# -404-19.net
KiCad netlist of a schematic drawn in Altium Designer
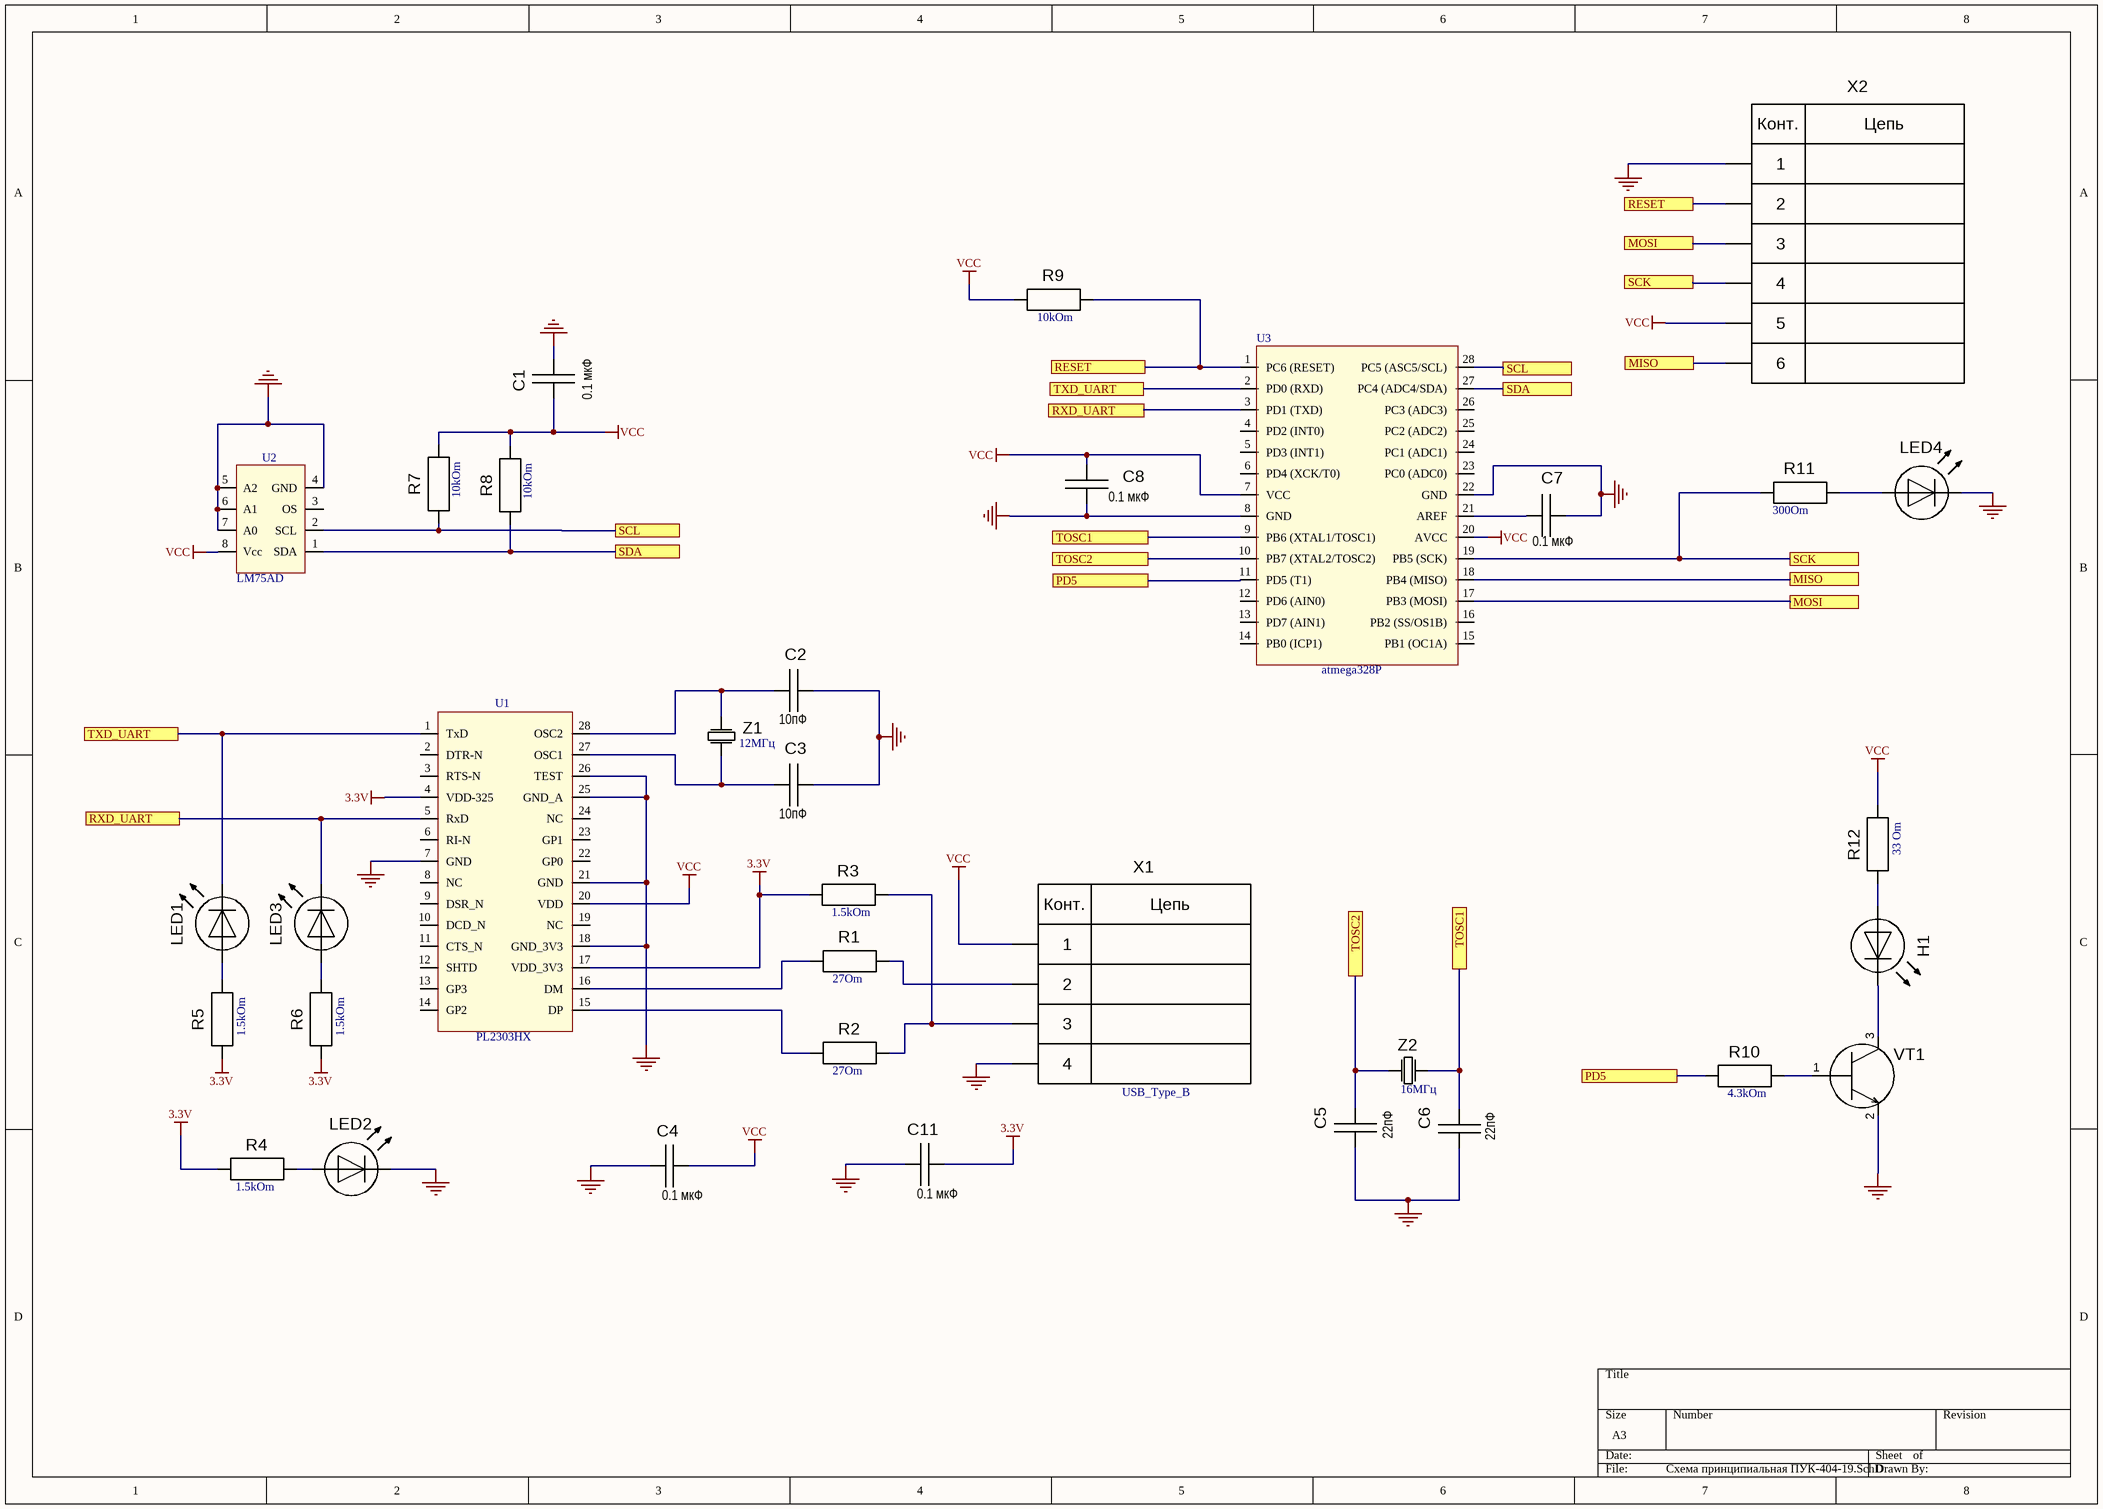
[diagram p0: Схема принципиальная ПУК-404-19.SchDoc]

(export (version "E")
  (design (tool "Eeschema 10.0.6"))
  (components
    (comp (ref "C1") (value "0.1 мкФ") (footprint "C_1206") (libsource (lib "") (part "C_1")))
    (comp (ref "C2") (value "10пФ") (footprint "C_0805") (libsource (lib "Passive") (part "C")))
    (comp (ref "C3") (value "10пФ") (footprint "C_0805") (libsource (lib "Passive") (part "C")))
    (comp (ref "C4") (value "0.1 мкФ") (footprint "C_1206") (libsource (lib "Passive") (part "C")))
    (comp (ref "C5") (value "22пФ") (footprint "C_1206") (libsource (lib "Passive") (part "C")))
    (comp (ref "C6") (value "22пФ") (footprint "C_1206") (libsource (lib "Passive") (part "C")))
    (comp (ref "C7") (value "0.1 мкФ") (footprint "C_1206") (libsource (lib "Passive") (part "C")))
    (comp (ref "C8") (value "0.1 мкФ") (footprint "C_1206") (libsource (lib "Passive") (part "C")))
    (comp (ref "C11") (value "0.1 мкФ") (footprint "C_1206") (libsource (lib "Passive") (part "C")))
    (comp (ref "H1") (value "TSAL6200") (footprint "ledrad3mm") (libsource (lib "VD") (part "LED")))
    (comp (ref "LED1") (value "LED") (footprint "ledrad3mm") (libsource (lib "VD") (part "LED")))
    (comp (ref "LED2") (value "LED") (footprint "ledrad3mm") (libsource (lib "VD") (part "LED")))
    (comp (ref "LED3") (value "LED") (footprint "ledrad3mm") (libsource (lib "VD") (part "LED")))
    (comp (ref "LED4") (value "LED") (footprint "ledrad3mm") (libsource (lib "VD") (part "LED")))
    (comp (ref "R1") (value "27Om") (footprint "R_1206") (libsource (lib "Passive") (part "Resistor")))
    (comp (ref "R2") (value "27Om") (footprint "R_1206") (libsource (lib "Passive") (part "Resistor")))
    (comp (ref "R3") (value "1.5kOm") (footprint "R_1206") (libsource (lib "Passive") (part "Resistor")))
    (comp (ref "R4") (value "1.5kOm") (footprint "R_1206") (libsource (lib "Passive") (part "Resistor")))
    (comp (ref "R5") (value "1.5kOm") (footprint "R_1206") (libsource (lib "Passive") (part "Resistor")))
    (comp (ref "R6") (value "1.5kOm") (footprint "R_1206") (libsource (lib "Passive") (part "Resistor")))
    (comp (ref "R7") (value "10kOm") (footprint "R_1206") (libsource (lib "Passive") (part "Resistor")))
    (comp (ref "R8") (value "10kOm") (footprint "R_1206") (libsource (lib "Passive") (part "Resistor")))
    (comp (ref "R9") (value "10kOm") (footprint "R_1206") (libsource (lib "Passive") (part "Resistor")))
    (comp (ref "R10") (value "4.3kOm") (footprint "R_1206") (libsource (lib "Passive") (part "Resistor")))
    (comp (ref "R11") (value "300Om") (footprint "R_1206") (libsource (lib "Passive") (part "Resistor")))
    (comp (ref "R12") (value "33 Om") (footprint "R_1206") (libsource (lib "Passive") (part "Resistor")))
    (comp (ref "U1") (value "PL2303HX") (footprint "SO-28W") (libsource (lib "PL2303HX") (part "PL2303HX")))
    (comp (ref "U2") (value "LM75AD") (footprint "TSSOP8") (libsource (lib "A75AD") (part "LM75AD")))
    (comp (ref "U3")
      (value "atmega328P")
      (footprint "27_DIP_7.62mm")
      (libsource (lib "ATMEGA328P") (part "Atmega328P"))
    )
    (comp (ref "VT1") (value "BC547") (footprint "TO-92-CBE") (libsource (lib "VT") (part "NPN_BEC")))
    (comp (ref "X1")
      (value "USB_Type_B")
      (footprint "USB_TypeB_Tyco")
      (libsource (lib "Connectors") (part "X_4"))
    )
    (comp (ref "X2") (value "X_6") (footprint "PLD-6") (libsource (lib "Connectors") (part "X_6")))
    (comp (ref "Z1") (value "12МГц") (footprint "HC-49H") (libsource (lib "") (part "Кварцевый резонатор_1")))
    (comp (ref "Z2") (value "16МГц") (footprint "HC-49H") (libsource (lib "Z") (part "Кварцевый резонатор")))
  )
  (nets
    (net (code "1") (name "/MISO") (class "Default")
      (node (ref "U3") (pin "18") (pinfunction "PB4_(MISO)_18") (pintype "passive"))
      (node (ref "X2") (pin "6") (pinfunction "6_6") (pintype "passive"))
    )
    (net (code "2") (name "/MOSI") (class "Default")
      (node (ref "U3") (pin "17") (pinfunction "PB3_(MOSI)_17") (pintype "passive"))
      (node (ref "X2") (pin "3") (pinfunction "3_3") (pintype "passive"))
    )
    (net (code "3") (name "/PD5") (class "Default")
      (node (ref "R10") (pin "1") (pinfunction "1_1") (pintype "passive"))
      (node (ref "U3") (pin "11") (pinfunction "PD5_(T1)_11") (pintype "passive"))
    )
    (net (code "4") (name "/RESET") (class "Default")
      (node (ref "R9") (pin "2") (pinfunction "2_2") (pintype "passive"))
      (node (ref "U3") (pin "1") (pinfunction "PC6_(RESET)_1") (pintype "passive"))
      (node (ref "X2") (pin "2") (pinfunction "2_2") (pintype "passive"))
    )
    (net (code "5") (name "/RXD_UART") (class "Default")
      (node (ref "LED3") (pin "2") (pinfunction "C_2") (pintype "passive"))
      (node (ref "U1") (pin "5") (pinfunction "RxD_5") (pintype "passive"))
      (node (ref "U3") (pin "3") (pinfunction "PD1_(TXD)_3") (pintype "passive"))
    )
    (net (code "6") (name "/SCK") (class "Default")
      (node (ref "R11") (pin "1") (pinfunction "1_1") (pintype "passive"))
      (node (ref "U3") (pin "19") (pinfunction "PB5_(SCK)_19") (pintype "passive"))
      (node (ref "X2") (pin "4") (pinfunction "4_4") (pintype "passive"))
    )
    (net (code "7") (name "/SCL") (class "Default")
      (node (ref "R7") (pin "1") (pinfunction "1_1") (pintype "passive"))
      (node (ref "U2") (pin "2") (pinfunction "SCL_2") (pintype "passive"))
      (node (ref "U3") (pin "28") (pinfunction "PC5_(ASC5/SCL)_28") (pintype "passive"))
    )
    (net (code "8") (name "/SDA") (class "Default")
      (node (ref "R8") (pin "1") (pinfunction "1_1") (pintype "passive"))
      (node (ref "U2") (pin "1") (pinfunction "SDA_1") (pintype "passive"))
      (node (ref "U3") (pin "27") (pinfunction "PC4_(ADC4/SDA)_27") (pintype "passive"))
    )
    (net (code "9") (name "/TOSC1") (class "Default")
      (node (ref "C6") (pin "2") (pinfunction "2_2") (pintype "passive"))
      (node (ref "U3") (pin "9") (pinfunction "PB6_(XTAL1/TOSC1)_9") (pintype "passive"))
      (node (ref "Z2") (pin "1") (pinfunction "X1_1") (pintype "passive"))
    )
    (net (code "10") (name "/TOSC2") (class "Default")
      (node (ref "C5") (pin "2") (pinfunction "2_2") (pintype "passive"))
      (node (ref "U3") (pin "10") (pinfunction "PB7_(XTAL2/TOSC2)_10") (pintype "passive"))
      (node (ref "Z2") (pin "2") (pinfunction "X2_2") (pintype "passive"))
    )
    (net (code "11") (name "/TXD_UART") (class "Default")
      (node (ref "LED1") (pin "2") (pinfunction "C_2") (pintype "passive"))
      (node (ref "U1") (pin "1") (pinfunction "TxD_1") (pintype "passive"))
      (node (ref "U3") (pin "2") (pinfunction "PD0_(RXD)_2") (pintype "passive"))
    )
    (net (code "12") (name "3.3V") (class "Default")
      (node (ref "C11") (pin "2") (pinfunction "2_2") (pintype "passive"))
      (node (ref "R3") (pin "1") (pinfunction "1_1") (pintype "passive"))
      (node (ref "R4") (pin "1") (pinfunction "1_1") (pintype "passive"))
      (node (ref "R5") (pin "1") (pinfunction "1_1") (pintype "passive"))
      (node (ref "R6") (pin "1") (pinfunction "1_1") (pintype "passive"))
      (node (ref "U1") (pin "17") (pinfunction "VDD_3V3_17") (pintype "passive"))
      (node (ref "U1") (pin "4") (pinfunction "VDD-325_4") (pintype "passive"))
    )
    (net (code "13") (name "GND") (class "Default")
      (node (ref "C1") (pin "2") (pinfunction "2_2") (pintype "passive"))
      (node (ref "C11") (pin "1") (pinfunction "1_1") (pintype "passive"))
      (node (ref "C2") (pin "2") (pinfunction "2_2") (pintype "passive"))
      (node (ref "C3") (pin "2") (pinfunction "2_2") (pintype "passive"))
      (node (ref "C4") (pin "1") (pinfunction "1_1") (pintype "passive"))
      (node (ref "C5") (pin "1") (pinfunction "1_1") (pintype "passive"))
      (node (ref "C6") (pin "1") (pinfunction "1_1") (pintype "passive"))
      (node (ref "C7") (pin "2") (pinfunction "2_2") (pintype "passive"))
      (node (ref "C8") (pin "1") (pinfunction "1_1") (pintype "passive"))
      (node (ref "LED2") (pin "2") (pinfunction "C_2") (pintype "passive"))
      (node (ref "LED4") (pin "2") (pinfunction "C_2") (pintype "passive"))
      (node (ref "U1") (pin "18") (pinfunction "GND_3V3_18") (pintype "passive"))
      (node (ref "U1") (pin "21") (pinfunction "GND_21") (pintype "passive"))
      (node (ref "U1") (pin "25") (pinfunction "GND_A_25") (pintype "passive"))
      (node (ref "U1") (pin "26") (pinfunction "TEST_26") (pintype "passive"))
      (node (ref "U1") (pin "7") (pinfunction "GND_7") (pintype "passive"))
      (node (ref "U2") (pin "4") (pinfunction "GND_4") (pintype "passive"))
      (node (ref "U2") (pin "5") (pinfunction "A2_5") (pintype "passive"))
      (node (ref "U2") (pin "6") (pinfunction "A1_6") (pintype "passive"))
      (node (ref "U2") (pin "7") (pinfunction "A0_7") (pintype "passive"))
      (node (ref "U3") (pin "22") (pinfunction "GND_22") (pintype "passive"))
      (node (ref "U3") (pin "8") (pinfunction "GND_8") (pintype "passive"))
      (node (ref "VT1") (pin "2") (pinfunction "2_2") (pintype "passive"))
      (node (ref "X1") (pin "4") (pinfunction "4_4") (pintype "passive"))
      (node (ref "X2") (pin "1") (pinfunction "1_1") (pintype "passive"))
    )
    (net (code "14") (name "Net-(H1-A)") (class "Default")
      (node (ref "H1") (pin "1") (pinfunction "A_1") (pintype "passive"))
      (node (ref "R12") (pin "1") (pinfunction "1_1") (pintype "passive"))
    )
    (net (code "15") (name "Net-(H1-C)") (class "Default")
      (node (ref "H1") (pin "2") (pinfunction "C_2") (pintype "passive"))
      (node (ref "VT1") (pin "3") (pinfunction "3_3") (pintype "passive"))
    )
    (net (code "16") (name "Net-(LED1-A)") (class "Default")
      (node (ref "LED1") (pin "1") (pinfunction "A_1") (pintype "passive"))
      (node (ref "R5") (pin "2") (pinfunction "2_2") (pintype "passive"))
    )
    (net (code "17") (name "Net-(LED2-A)") (class "Default")
      (node (ref "LED2") (pin "1") (pinfunction "A_1") (pintype "passive"))
      (node (ref "R4") (pin "2") (pinfunction "2_2") (pintype "passive"))
    )
    (net (code "18") (name "Net-(LED3-A)") (class "Default")
      (node (ref "LED3") (pin "1") (pinfunction "A_1") (pintype "passive"))
      (node (ref "R6") (pin "2") (pinfunction "2_2") (pintype "passive"))
    )
    (net (code "19") (name "Net-(LED4-A)") (class "Default")
      (node (ref "LED4") (pin "1") (pinfunction "A_1") (pintype "passive"))
      (node (ref "R11") (pin "2") (pinfunction "2_2") (pintype "passive"))
    )
    (net (code "20") (name "Net-(R1-Pad2)") (class "Default")
      (node (ref "R1") (pin "2") (pinfunction "2_2") (pintype "passive"))
      (node (ref "X1") (pin "2") (pinfunction "2_2") (pintype "passive"))
    )
    (net (code "21") (name "Net-(R2-Pad2)") (class "Default")
      (node (ref "R2") (pin "2") (pinfunction "2_2") (pintype "passive"))
      (node (ref "R3") (pin "2") (pinfunction "2_2") (pintype "passive"))
      (node (ref "X1") (pin "3") (pinfunction "3_3") (pintype "passive"))
    )
    (net (code "22") (name "Net-(R10-Pad2)") (class "Default")
      (node (ref "R10") (pin "2") (pinfunction "2_2") (pintype "passive"))
      (node (ref "VT1") (pin "1") (pinfunction "1_1") (pintype "passive"))
    )
    (net (code "23") (name "Net-(U1-DM)") (class "Default")
      (node (ref "R1") (pin "1") (pinfunction "1_1") (pintype "passive"))
      (node (ref "U1") (pin "16") (pinfunction "DM_16") (pintype "passive"))
    )
    (net (code "24") (name "Net-(U1-DP)") (class "Default")
      (node (ref "R2") (pin "1") (pinfunction "1_1") (pintype "passive"))
      (node (ref "U1") (pin "15") (pinfunction "DP_15") (pintype "passive"))
    )
    (net (code "25") (name "Net-(U1-OSC1)") (class "Default")
      (node (ref "C3") (pin "1") (pinfunction "1_1") (pintype "passive"))
      (node (ref "U1") (pin "27") (pinfunction "OSC1_27") (pintype "passive"))
      (node (ref "Z1") (pin "1") (pinfunction "X1_1") (pintype "passive"))
    )
    (net (code "26") (name "Net-(U1-OSC2)") (class "Default")
      (node (ref "C2") (pin "1") (pinfunction "1_1") (pintype "passive"))
      (node (ref "U1") (pin "28") (pinfunction "OSC2_28") (pintype "passive"))
      (node (ref "Z1") (pin "2") (pinfunction "X2_2") (pintype "passive"))
    )
    (net (code "27") (name "Net-(U3-AREF)") (class "Default")
      (node (ref "C7") (pin "1") (pinfunction "1_1") (pintype "passive"))
      (node (ref "U3") (pin "21") (pinfunction "AREF_21") (pintype "passive"))
    )
    (net (code "28") (name "VCC") (class "Default")
      (node (ref "C1") (pin "1") (pinfunction "1_1") (pintype "passive"))
      (node (ref "C4") (pin "2") (pinfunction "2_2") (pintype "passive"))
      (node (ref "C8") (pin "2") (pinfunction "2_2") (pintype "passive"))
      (node (ref "R12") (pin "2") (pinfunction "2_2") (pintype "passive"))
      (node (ref "R7") (pin "2") (pinfunction "2_2") (pintype "passive"))
      (node (ref "R8") (pin "2") (pinfunction "2_2") (pintype "passive"))
      (node (ref "R9") (pin "1") (pinfunction "1_1") (pintype "passive"))
      (node (ref "U1") (pin "20") (pinfunction "VDD_20") (pintype "passive"))
      (node (ref "U2") (pin "8") (pinfunction "Vcc_8") (pintype "passive"))
      (node (ref "U3") (pin "20") (pinfunction "AVCC_20") (pintype "passive"))
      (node (ref "U3") (pin "7") (pinfunction "VCC_7") (pintype "passive"))
      (node (ref "X1") (pin "1") (pinfunction "1_1") (pintype "passive"))
      (node (ref "X2") (pin "5") (pinfunction "5_5") (pintype "passive"))
    )
    (net (code "29") (name "unconnected-(U1-CTS_N-Pad11)") (class "Default")
      (node (ref "U1") (pin "11") (pinfunction "CTS_N_11") (pintype "passive"))
    )
    (net (code "30") (name "unconnected-(U1-DCD_N-Pad10)") (class "Default")
      (node (ref "U1") (pin "10") (pinfunction "DCD_N_10") (pintype "passive"))
    )
    (net (code "31") (name "unconnected-(U1-DSR_N-Pad9)") (class "Default")
      (node (ref "U1") (pin "9") (pinfunction "DSR_N_9") (pintype "passive"))
    )
    (net (code "32") (name "unconnected-(U1-DTR-N-Pad2)") (class "Default")
      (node (ref "U1") (pin "2") (pinfunction "DTR-N_2") (pintype "passive"))
    )
    (net (code "33") (name "unconnected-(U1-GP0-Pad22)") (class "Default")
      (node (ref "U1") (pin "22") (pinfunction "GP0_22") (pintype "passive"))
    )
    (net (code "34") (name "unconnected-(U1-GP1-Pad23)") (class "Default")
      (node (ref "U1") (pin "23") (pinfunction "GP1_23") (pintype "passive"))
    )
    (net (code "35") (name "unconnected-(U1-GP2-Pad14)") (class "Default")
      (node (ref "U1") (pin "14") (pinfunction "GP2_14") (pintype "passive"))
    )
    (net (code "36") (name "unconnected-(U1-GP3-Pad13)") (class "Default")
      (node (ref "U1") (pin "13") (pinfunction "GP3_13") (pintype "passive"))
    )
    (net (code "37") (name "unconnected-(U1-NC-Pad8)") (class "Default")
      (node (ref "U1") (pin "8") (pinfunction "NC_8") (pintype "passive"))
    )
    (net (code "38") (name "unconnected-(U1-NC-Pad19)") (class "Default")
      (node (ref "U1") (pin "19") (pinfunction "NC_19") (pintype "passive"))
    )
    (net (code "39") (name "unconnected-(U1-NC-Pad24)") (class "Default")
      (node (ref "U1") (pin "24") (pinfunction "NC_24") (pintype "passive"))
    )
    (net (code "40") (name "unconnected-(U1-RI-N-Pad6)") (class "Default")
      (node (ref "U1") (pin "6") (pinfunction "RI-N_6") (pintype "passive"))
    )
    (net (code "41") (name "unconnected-(U1-RTS-N-Pad3)") (class "Default")
      (node (ref "U1") (pin "3") (pinfunction "RTS-N_3") (pintype "passive"))
    )
    (net (code "42") (name "unconnected-(U1-SHTD-Pad12)") (class "Default")
      (node (ref "U1") (pin "12") (pinfunction "SHTD_12") (pintype "passive"))
    )
    (net (code "43") (name "unconnected-(U2-OS-Pad3)") (class "Default")
      (node (ref "U2") (pin "3") (pinfunction "OS_3") (pintype "passive"))
    )
    (net (code "44") (name "unconnected-(U3-PB0_(ICP1)-Pad14)") (class "Default")
      (node (ref "U3") (pin "14") (pinfunction "PB0_(ICP1)_14") (pintype "passive"))
    )
    (net (code "45") (name "unconnected-(U3-PB1_(OC1A)-Pad15)") (class "Default")
      (node (ref "U3") (pin "15") (pinfunction "PB1_(OC1A)_15") (pintype "passive"))
    )
    (net (code "46") (name "unconnected-(U3-PB2_(SS{slash}OS1B)-Pad16)") (class "Default")
      (node (ref "U3") (pin "16") (pinfunction "PB2_(SS/OS1B)_16") (pintype "passive"))
    )
    (net (code "47") (name "unconnected-(U3-PC0_(ADC0)-Pad23)") (class "Default")
      (node (ref "U3") (pin "23") (pinfunction "PC0_(ADC0)_23") (pintype "passive"))
    )
    (net (code "48") (name "unconnected-(U3-PC1_(ADC1)-Pad24)") (class "Default")
      (node (ref "U3") (pin "24") (pinfunction "PC1_(ADC1)_24") (pintype "passive"))
    )
    (net (code "49") (name "unconnected-(U3-PC2_(ADC2)-Pad25)") (class "Default")
      (node (ref "U3") (pin "25") (pinfunction "PC2_(ADC2)_25") (pintype "passive"))
    )
    (net (code "50") (name "unconnected-(U3-PC3_(ADC3)-Pad26)") (class "Default")
      (node (ref "U3") (pin "26") (pinfunction "PC3_(ADC3)_26") (pintype "passive"))
    )
    (net (code "51") (name "unconnected-(U3-PD2_(INT0)-Pad4)") (class "Default")
      (node (ref "U3") (pin "4") (pinfunction "PD2_(INT0)_4") (pintype "passive"))
    )
    (net (code "52") (name "unconnected-(U3-PD3_(INT1)-Pad5)") (class "Default")
      (node (ref "U3") (pin "5") (pinfunction "PD3_(INT1)_5") (pintype "passive"))
    )
    (net (code "53") (name "unconnected-(U3-PD4_(XCK{slash}T0)-Pad6)") (class "Default")
      (node (ref "U3") (pin "6") (pinfunction "PD4_(XCK/T0)_6") (pintype "passive"))
    )
    (net (code "54") (name "unconnected-(U3-PD6_(AIN0)-Pad12)") (class "Default")
      (node (ref "U3") (pin "12") (pinfunction "PD6_(AIN0)_12") (pintype "passive"))
    )
    (net (code "55") (name "unconnected-(U3-PD7_(AIN1)-Pad13)") (class "Default")
      (node (ref "U3") (pin "13") (pinfunction "PD7_(AIN1)_13") (pintype "passive"))
    )
  )
)
